# HuUSB_rev_B.net
KiCad netlist of a schematic drawn in EAGLE
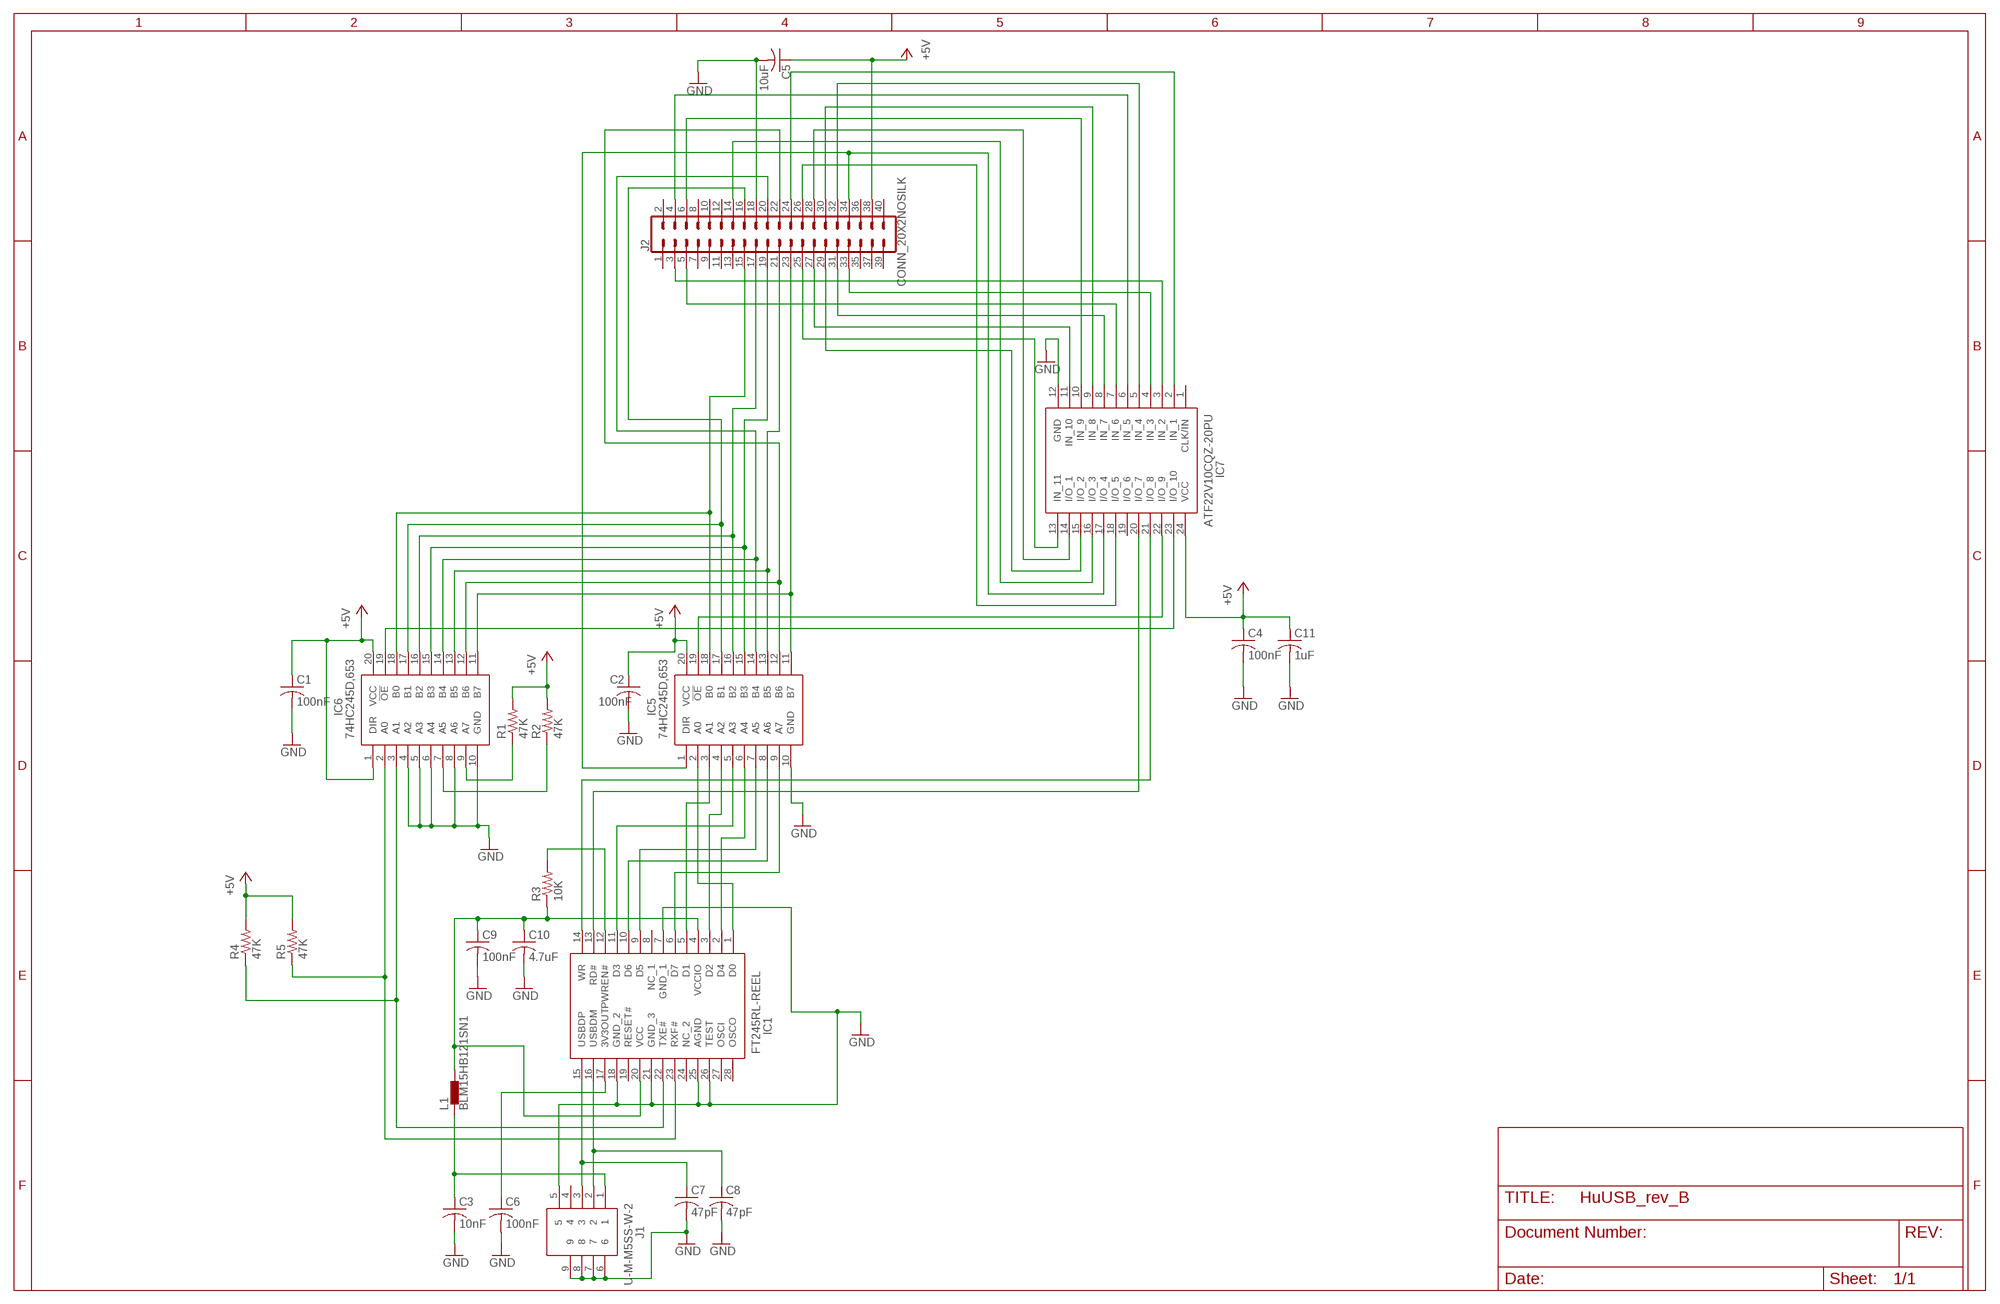
[diagram p0: schematic, sheet 1]

(export (version "E")
  (design (tool "Eeschema 10.0.6"))
  (components
    (comp (ref "C1")
      (value "100nF")
      (footprint "eagle-import:C0603")
      (libsource (lib "eagle-import") (part "C-USC0603"))
    )
    (comp (ref "C2")
      (value "100nF")
      (footprint "eagle-import:C0603")
      (libsource (lib "eagle-import") (part "C-USC0603"))
    )
    (comp (ref "C3")
      (value "10nF")
      (footprint "eagle-import:C0603")
      (libsource (lib "eagle-import") (part "C-USC0603"))
    )
    (comp (ref "C4")
      (value "100nF")
      (footprint "eagle-import:C0603")
      (libsource (lib "eagle-import") (part "C-USC0603"))
    )
    (comp (ref "C5")
      (value "10uF")
      (footprint "eagle-import:C0805")
      (libsource (lib "eagle-import") (part "C-USC0805"))
    )
    (comp (ref "C6")
      (value "100nF")
      (footprint "eagle-import:C0603")
      (libsource (lib "eagle-import") (part "C-USC0603"))
    )
    (comp (ref "C7")
      (value "47pF")
      (footprint "eagle-import:C0603")
      (libsource (lib "eagle-import") (part "C-USC0603"))
    )
    (comp (ref "C8")
      (value "47pF")
      (footprint "eagle-import:C0603")
      (libsource (lib "eagle-import") (part "C-USC0603"))
    )
    (comp (ref "C9")
      (value "100nF")
      (footprint "eagle-import:C0603")
      (libsource (lib "eagle-import") (part "C-USC0603"))
    )
    (comp (ref "C10")
      (value "4.7uF")
      (footprint "eagle-import:C0603")
      (libsource (lib "eagle-import") (part "C-USC0603"))
    )
    (comp (ref "C11")
      (value "1uF")
      (footprint "eagle-import:C0603")
      (libsource (lib "eagle-import") (part "C-USC0603"))
    )
    (comp (ref "IC1")
      (value "FT245RL-REEL")
      (footprint "eagle-import:SOP65P778X200-28N")
      (fields (field (name "MOUSER_PART_NUMBER") "895-FT245RL"))
      (libsource (lib "eagle-import") (part "FT245RL-REEL"))
    )
    (comp (ref "IC5")
      (value "74HC245D,653")
      (footprint "eagle-import:SOIC127P1032X265-20N")
      (fields (field (name "MOUSER_PART_NUMBER") "771-74HC245D-T"))
      (libsource (lib "eagle-import") (part "74HC245D,653"))
    )
    (comp (ref "IC6")
      (value "74HC245D,653")
      (footprint "eagle-import:SOIC127P1032X265-20N")
      (fields (field (name "MOUSER_PART_NUMBER") "771-74HC245D-T"))
      (libsource (lib "eagle-import") (part "74HC245D,653"))
    )
    (comp (ref "IC7")
      (value "ATF22V10CQZ-20PU")
      (footprint "eagle-import:DIP794W56P254L3188H533Q24N")
      (fields (field (name "MOUSER_PART_NUMBER") "556-AF22V10CQZ-20PU"))
      (libsource (lib "eagle-import") (part "ATF22V10CQZ-20PU"))
    )
    (comp (ref "J1")
      (value "U-M-M5SS-W-2")
      (footprint "eagle-import:U-M-M5SS-W-2")
      (libsource (lib "eagle-import") (part "U-M-M5SS-W-2"))
    )
    (comp (ref "J2")
      (value "CONN_20X2NOSILK")
      (footprint "eagle-import:2X20_NOSILK")
      (libsource (lib "eagle-import") (part "CONN_20X2NOSILK"))
    )
    (comp (ref "L1")
      (value "BLM15HB121SN1")
      (footprint "eagle-import:0402")
      (libsource (lib "eagle-import") (part "BLM15HB121SN1"))
    )
    (comp (ref "R1")
      (value "47K")
      (footprint "eagle-import:R0603")
      (libsource (lib "eagle-import") (part "R-US_R0603"))
    )
    (comp (ref "R2")
      (value "47K")
      (footprint "eagle-import:R0603")
      (libsource (lib "eagle-import") (part "R-US_R0603"))
    )
    (comp (ref "R3")
      (value "10K")
      (footprint "eagle-import:R0603")
      (libsource (lib "eagle-import") (part "R-US_R0603"))
    )
    (comp (ref "R4")
      (value "47K")
      (footprint "eagle-import:R0603")
      (libsource (lib "eagle-import") (part "R-US_R0603"))
    )
    (comp (ref "R5")
      (value "47K")
      (footprint "eagle-import:R0603")
      (libsource (lib "eagle-import") (part "R-US_R0603"))
    )
  )
  (nets
    (net (code "1") (name "+5V") (class "Default")
      (node (ref "C1") (pin "1") (pinfunction "1_1") (pintype "passive"))
      (node (ref "C11") (pin "1") (pinfunction "1_1") (pintype "passive"))
      (node (ref "C2") (pin "1") (pinfunction "1_1") (pintype "passive"))
      (node (ref "C4") (pin "1") (pinfunction "1_1") (pintype "passive"))
      (node (ref "C5") (pin "1") (pinfunction "1_1") (pintype "passive"))
      (node (ref "IC5") (pin "20") (pinfunction "VCC_20") (pintype "bidirectional"))
      (node (ref "IC6") (pin "1") (pinfunction "DIR_1") (pintype "bidirectional"))
      (node (ref "IC6") (pin "20") (pinfunction "VCC_20") (pintype "bidirectional"))
      (node (ref "IC7") (pin "24") (pinfunction "VCC_24") (pintype "bidirectional"))
      (node (ref "J2") (pin "38") (pinfunction "38_38") (pintype "passive"))
      (node (ref "R1") (pin "2") (pinfunction "2_2") (pintype "passive"))
      (node (ref "R2") (pin "2") (pinfunction "2_2") (pintype "passive"))
      (node (ref "R4") (pin "2") (pinfunction "2_2") (pintype "passive"))
      (node (ref "R5") (pin "2") (pinfunction "2_2") (pintype "passive"))
    )
    (net (code "2") (name "GND") (class "Default")
      (node (ref "C1") (pin "2") (pinfunction "2_2") (pintype "passive"))
      (node (ref "C10") (pin "2") (pinfunction "2_2") (pintype "passive"))
      (node (ref "C11") (pin "2") (pinfunction "2_2") (pintype "passive"))
      (node (ref "C2") (pin "2") (pinfunction "2_2") (pintype "passive"))
      (node (ref "C3") (pin "2") (pinfunction "2_2") (pintype "passive"))
      (node (ref "C4") (pin "2") (pinfunction "2_2") (pintype "passive"))
      (node (ref "C5") (pin "2") (pinfunction "2_2") (pintype "passive"))
      (node (ref "C6") (pin "2") (pinfunction "2_2") (pintype "passive"))
      (node (ref "C7") (pin "2") (pinfunction "2_2") (pintype "passive"))
      (node (ref "C8") (pin "2") (pinfunction "2_2") (pintype "passive"))
      (node (ref "C9") (pin "2") (pinfunction "2_2") (pintype "passive"))
      (node (ref "IC1") (pin "18") (pinfunction "GND_2_18") (pintype "bidirectional"))
      (node (ref "IC1") (pin "21") (pinfunction "GND_3_21") (pintype "bidirectional"))
      (node (ref "IC1") (pin "25") (pinfunction "AGND_25") (pintype "bidirectional"))
      (node (ref "IC1") (pin "26") (pinfunction "TEST_26") (pintype "bidirectional"))
      (node (ref "IC1") (pin "7") (pinfunction "GND_1_7") (pintype "bidirectional"))
      (node (ref "IC5") (pin "10") (pinfunction "GND_10") (pintype "bidirectional"))
      (node (ref "IC6") (pin "10") (pinfunction "GND_10") (pintype "bidirectional"))
      (node (ref "IC6") (pin "4") (pinfunction "A2_4") (pintype "bidirectional"))
      (node (ref "IC6") (pin "5") (pinfunction "A3_5") (pintype "bidirectional"))
      (node (ref "IC6") (pin "6") (pinfunction "A4_6") (pintype "bidirectional"))
      (node (ref "IC6") (pin "8") (pinfunction "A6_8") (pintype "bidirectional"))
      (node (ref "IC7") (pin "12") (pinfunction "GND_12") (pintype "bidirectional"))
      (node (ref "J1") (pin "5") (pinfunction "5_5") (pintype "bidirectional"))
      (node (ref "J1") (pin "6") (pinfunction "6_6") (pintype "bidirectional"))
      (node (ref "J1") (pin "7") (pinfunction "7_7") (pintype "bidirectional"))
      (node (ref "J1") (pin "8") (pinfunction "8_8") (pintype "bidirectional"))
      (node (ref "J1") (pin "9") (pinfunction "9_9") (pintype "bidirectional"))
      (node (ref "J2") (pin "18") (pinfunction "18_18") (pintype "passive"))
    )
    (net (code "3") (name "Net-(C3-Pad1)") (class "Default")
      (node (ref "C3") (pin "1") (pinfunction "1_1") (pintype "passive"))
      (node (ref "J1") (pin "1") (pinfunction "1_1") (pintype "bidirectional"))
      (node (ref "L1") (pin "1") (pinfunction "1_1") (pintype "passive"))
    )
    (net (code "4") (name "Net-(IC1-3V3OUT)") (class "Default")
      (node (ref "C6") (pin "1") (pinfunction "1_1") (pintype "passive"))
      (node (ref "IC1") (pin "17") (pinfunction "3V3OUT_17") (pintype "bidirectional"))
    )
    (net (code "5") (name "Net-(IC1-D0)") (class "Default")
      (node (ref "IC1") (pin "1") (pinfunction "D0_1") (pintype "bidirectional"))
      (node (ref "IC5") (pin "2") (pinfunction "A0_2") (pintype "bidirectional"))
    )
    (net (code "6") (name "Net-(IC1-D1)") (class "Default")
      (node (ref "IC1") (pin "5") (pinfunction "D1_5") (pintype "bidirectional"))
      (node (ref "IC5") (pin "3") (pinfunction "A1_3") (pintype "bidirectional"))
    )
    (net (code "7") (name "Net-(IC1-D2)") (class "Default")
      (node (ref "IC1") (pin "3") (pinfunction "D2_3") (pintype "bidirectional"))
      (node (ref "IC5") (pin "4") (pinfunction "A2_4") (pintype "bidirectional"))
    )
    (net (code "8") (name "Net-(IC1-D3)") (class "Default")
      (node (ref "IC1") (pin "11") (pinfunction "D3_11") (pintype "bidirectional"))
      (node (ref "IC5") (pin "5") (pinfunction "A3_5") (pintype "bidirectional"))
    )
    (net (code "9") (name "Net-(IC1-D4)") (class "Default")
      (node (ref "IC1") (pin "2") (pinfunction "D4_2") (pintype "bidirectional"))
      (node (ref "IC5") (pin "6") (pinfunction "A4_6") (pintype "bidirectional"))
    )
    (net (code "10") (name "Net-(IC1-D5)") (class "Default")
      (node (ref "IC1") (pin "9") (pinfunction "D5_9") (pintype "bidirectional"))
      (node (ref "IC5") (pin "7") (pinfunction "A5_7") (pintype "bidirectional"))
    )
    (net (code "11") (name "Net-(IC1-D6)") (class "Default")
      (node (ref "IC1") (pin "10") (pinfunction "D6_10") (pintype "bidirectional"))
      (node (ref "IC5") (pin "8") (pinfunction "A6_8") (pintype "bidirectional"))
    )
    (net (code "12") (name "Net-(IC1-D7)") (class "Default")
      (node (ref "IC1") (pin "6") (pinfunction "D7_6") (pintype "bidirectional"))
      (node (ref "IC5") (pin "9") (pinfunction "A7_9") (pintype "bidirectional"))
    )
    (net (code "13") (name "Net-(IC1-PWREN#)") (class "Default")
      (node (ref "IC1") (pin "12") (pinfunction "PWREN#_12") (pintype "bidirectional"))
      (node (ref "R3") (pin "2") (pinfunction "2_2") (pintype "passive"))
    )
    (net (code "14") (name "Net-(IC1-RD#)") (class "Default")
      (node (ref "IC1") (pin "13") (pinfunction "RD#_13") (pintype "bidirectional"))
      (node (ref "IC7") (pin "20") (pinfunction "I/O_7_20") (pintype "bidirectional"))
    )
    (net (code "15") (name "Net-(IC1-RXF#)") (class "Default")
      (node (ref "IC1") (pin "23") (pinfunction "RXF#_23") (pintype "bidirectional"))
      (node (ref "IC6") (pin "2") (pinfunction "A0_2") (pintype "bidirectional"))
      (node (ref "R5") (pin "1") (pinfunction "1_1") (pintype "passive"))
    )
    (net (code "16") (name "Net-(IC1-TXE#)") (class "Default")
      (node (ref "IC1") (pin "22") (pinfunction "TXE#_22") (pintype "bidirectional"))
      (node (ref "IC6") (pin "3") (pinfunction "A1_3") (pintype "bidirectional"))
      (node (ref "R4") (pin "1") (pinfunction "1_1") (pintype "passive"))
    )
    (net (code "17") (name "Net-(IC1-USBDM)") (class "Default")
      (node (ref "C8") (pin "1") (pinfunction "1_1") (pintype "passive"))
      (node (ref "IC1") (pin "16") (pinfunction "USBDM_16") (pintype "bidirectional"))
      (node (ref "J1") (pin "2") (pinfunction "2_2") (pintype "bidirectional"))
    )
    (net (code "18") (name "Net-(IC1-USBDP)") (class "Default")
      (node (ref "C7") (pin "1") (pinfunction "1_1") (pintype "passive"))
      (node (ref "IC1") (pin "15") (pinfunction "USBDP_15") (pintype "bidirectional"))
      (node (ref "J1") (pin "3") (pinfunction "3_3") (pintype "bidirectional"))
    )
    (net (code "19") (name "Net-(IC1-VCC)") (class "Default")
      (node (ref "C10") (pin "1") (pinfunction "1_1") (pintype "passive"))
      (node (ref "C9") (pin "1") (pinfunction "1_1") (pintype "passive"))
      (node (ref "IC1") (pin "20") (pinfunction "VCC_20") (pintype "bidirectional"))
      (node (ref "IC1") (pin "4") (pinfunction "VCCIO_4") (pintype "bidirectional"))
      (node (ref "L1") (pin "2") (pinfunction "2_2") (pintype "passive"))
      (node (ref "R3") (pin "1") (pinfunction "1_1") (pintype "passive"))
    )
    (net (code "20") (name "Net-(IC1-WR)") (class "Default")
      (node (ref "IC1") (pin "14") (pinfunction "WR_14") (pintype "bidirectional"))
      (node (ref "IC7") (pin "21") (pinfunction "I/O_8_21") (pintype "bidirectional"))
    )
    (net (code "21") (name "Net-(IC5-B0)") (class "Default")
      (node (ref "IC5") (pin "18") (pinfunction "B0_18") (pintype "bidirectional"))
      (node (ref "IC6") (pin "18") (pinfunction "B0_18") (pintype "bidirectional"))
      (node (ref "J2") (pin "15") (pinfunction "15_15") (pintype "passive"))
    )
    (net (code "22") (name "Net-(IC5-B1)") (class "Default")
      (node (ref "IC5") (pin "17") (pinfunction "B1_17") (pintype "bidirectional"))
      (node (ref "IC6") (pin "17") (pinfunction "B1_17") (pintype "bidirectional"))
      (node (ref "J2") (pin "16") (pinfunction "16_16") (pintype "passive"))
    )
    (net (code "23") (name "Net-(IC5-B2)") (class "Default")
      (node (ref "IC5") (pin "16") (pinfunction "B2_16") (pintype "bidirectional"))
      (node (ref "IC6") (pin "16") (pinfunction "B2_16") (pintype "bidirectional"))
      (node (ref "J2") (pin "17") (pinfunction "17_17") (pintype "passive"))
    )
    (net (code "24") (name "Net-(IC5-B3)") (class "Default")
      (node (ref "IC5") (pin "15") (pinfunction "B3_15") (pintype "bidirectional"))
      (node (ref "IC6") (pin "15") (pinfunction "B3_15") (pintype "bidirectional"))
      (node (ref "J2") (pin "19") (pinfunction "19_19") (pintype "passive"))
    )
    (net (code "25") (name "Net-(IC5-B4)") (class "Default")
      (node (ref "IC5") (pin "14") (pinfunction "B4_14") (pintype "bidirectional"))
      (node (ref "IC6") (pin "14") (pinfunction "B4_14") (pintype "bidirectional"))
      (node (ref "J2") (pin "20") (pinfunction "20_20") (pintype "passive"))
    )
    (net (code "26") (name "Net-(IC5-B5)") (class "Default")
      (node (ref "IC5") (pin "13") (pinfunction "B5_13") (pintype "bidirectional"))
      (node (ref "IC6") (pin "13") (pinfunction "B5_13") (pintype "bidirectional"))
      (node (ref "J2") (pin "21") (pinfunction "21_21") (pintype "passive"))
    )
    (net (code "27") (name "Net-(IC5-B6)") (class "Default")
      (node (ref "IC5") (pin "12") (pinfunction "B6_12") (pintype "bidirectional"))
      (node (ref "IC6") (pin "12") (pinfunction "B6_12") (pintype "bidirectional"))
      (node (ref "J2") (pin "22") (pinfunction "22_22") (pintype "passive"))
    )
    (net (code "28") (name "Net-(IC5-B7)") (class "Default")
      (node (ref "IC5") (pin "11") (pinfunction "B7_11") (pintype "bidirectional"))
      (node (ref "IC6") (pin "11") (pinfunction "B7_11") (pintype "bidirectional"))
      (node (ref "J2") (pin "23") (pinfunction "23_23") (pintype "passive"))
    )
    (net (code "29") (name "Net-(IC5-DIR)") (class "Default")
      (node (ref "IC5") (pin "1") (pinfunction "DIR_1") (pintype "bidirectional"))
      (node (ref "IC7") (pin "17") (pinfunction "I/O_4_17") (pintype "bidirectional"))
      (node (ref "J2") (pin "34") (pinfunction "34_34") (pintype "passive"))
    )
    (net (code "30") (name "Net-(IC5-~{OE})") (class "Default")
      (node (ref "IC5") (pin "19") (pinfunction "~{OE}_19") (pintype "bidirectional"))
      (node (ref "IC7") (pin "22") (pinfunction "I/O_9_22") (pintype "bidirectional"))
    )
    (net (code "31") (name "Net-(IC6-A5)") (class "Default")
      (node (ref "IC6") (pin "7") (pinfunction "A5_7") (pintype "bidirectional"))
      (node (ref "R2") (pin "1") (pinfunction "1_1") (pintype "passive"))
    )
    (net (code "32") (name "Net-(IC6-A7)") (class "Default")
      (node (ref "IC6") (pin "9") (pinfunction "A7_9") (pintype "bidirectional"))
      (node (ref "R1") (pin "1") (pinfunction "1_1") (pintype "passive"))
    )
    (net (code "33") (name "Net-(IC6-~{OE})") (class "Default")
      (node (ref "IC6") (pin "19") (pinfunction "~{OE}_19") (pintype "bidirectional"))
      (node (ref "IC7") (pin "23") (pinfunction "I/O_10_23") (pintype "bidirectional"))
    )
    (net (code "34") (name "Net-(IC7-IN_1)") (class "Default")
      (node (ref "IC7") (pin "2") (pinfunction "IN_1_2") (pintype "bidirectional"))
      (node (ref "J2") (pin "24") (pinfunction "24_24") (pintype "passive"))
    )
    (net (code "35") (name "Net-(IC7-IN_2)") (class "Default")
      (node (ref "IC7") (pin "3") (pinfunction "IN_2_3") (pintype "bidirectional"))
      (node (ref "J2") (pin "3") (pinfunction "3_3") (pintype "passive"))
    )
    (net (code "36") (name "Net-(IC7-IN_3)") (class "Default")
      (node (ref "IC7") (pin "4") (pinfunction "IN_3_4") (pintype "bidirectional"))
      (node (ref "J2") (pin "33") (pinfunction "33_33") (pintype "passive"))
    )
    (net (code "37") (name "Net-(IC7-IN_4)") (class "Default")
      (node (ref "IC7") (pin "5") (pinfunction "IN_4_5") (pintype "bidirectional"))
      (node (ref "J2") (pin "32") (pinfunction "32_32") (pintype "passive"))
    )
    (net (code "38") (name "Net-(IC7-IN_5)") (class "Default")
      (node (ref "IC7") (pin "6") (pinfunction "IN_5_6") (pintype "bidirectional"))
      (node (ref "J2") (pin "4") (pinfunction "4_4") (pintype "passive"))
    )
    (net (code "39") (name "Net-(IC7-IN_6)") (class "Default")
      (node (ref "IC7") (pin "7") (pinfunction "IN_6_7") (pintype "bidirectional"))
      (node (ref "J2") (pin "5") (pinfunction "5_5") (pintype "passive"))
    )
    (net (code "40") (name "Net-(IC7-IN_7)") (class "Default")
      (node (ref "IC7") (pin "8") (pinfunction "IN_7_8") (pintype "bidirectional"))
      (node (ref "J2") (pin "31") (pinfunction "31_31") (pintype "passive"))
    )
    (net (code "41") (name "Net-(IC7-IN_8)") (class "Default")
      (node (ref "IC7") (pin "9") (pinfunction "IN_8_9") (pintype "bidirectional"))
      (node (ref "J2") (pin "30") (pinfunction "30_30") (pintype "passive"))
    )
    (net (code "42") (name "Net-(IC7-IN_9)") (class "Default")
      (node (ref "IC7") (pin "10") (pinfunction "IN_9_10") (pintype "bidirectional"))
      (node (ref "J2") (pin "6") (pinfunction "6_6") (pintype "passive"))
    )
    (net (code "43") (name "Net-(IC7-IN_10)") (class "Default")
      (node (ref "IC7") (pin "11") (pinfunction "IN_10_11") (pintype "bidirectional"))
      (node (ref "J2") (pin "27") (pinfunction "27_27") (pintype "passive"))
    )
    (net (code "44") (name "Net-(IC7-IN_11)") (class "Default")
      (node (ref "IC7") (pin "13") (pinfunction "IN_11_13") (pintype "bidirectional"))
      (node (ref "J2") (pin "25") (pinfunction "25_25") (pintype "passive"))
    )
    (net (code "45") (name "Net-(IC7-I{slash}O_1)") (class "Default")
      (node (ref "IC7") (pin "14") (pinfunction "I/O_1_14") (pintype "bidirectional"))
      (node (ref "J2") (pin "28") (pinfunction "28_28") (pintype "passive"))
    )
    (net (code "46") (name "Net-(IC7-I{slash}O_2)") (class "Default")
      (node (ref "IC7") (pin "15") (pinfunction "I/O_2_15") (pintype "bidirectional"))
      (node (ref "J2") (pin "29") (pinfunction "29_29") (pintype "passive"))
    )
    (net (code "47") (name "Net-(IC7-I{slash}O_3)") (class "Default")
      (node (ref "IC7") (pin "16") (pinfunction "I/O_3_16") (pintype "bidirectional"))
      (node (ref "J2") (pin "14") (pinfunction "14_14") (pintype "passive"))
    )
    (net (code "48") (name "Net-(IC7-I{slash}O_5)") (class "Default")
      (node (ref "IC7") (pin "18") (pinfunction "I/O_5_18") (pintype "bidirectional"))
      (node (ref "J2") (pin "26") (pinfunction "26_26") (pintype "passive"))
    )
    (net (code "49") (name "unconnected-(IC1-NC_1-Pad8)") (class "Default")
      (node (ref "IC1") (pin "8") (pinfunction "NC_1_8") (pintype "bidirectional"))
    )
    (net (code "50") (name "unconnected-(IC1-NC_2-Pad24)") (class "Default")
      (node (ref "IC1") (pin "24") (pinfunction "NC_2_24") (pintype "bidirectional"))
    )
    (net (code "51") (name "unconnected-(IC1-OSCI-Pad27)") (class "Default")
      (node (ref "IC1") (pin "27") (pinfunction "OSCI_27") (pintype "bidirectional"))
    )
    (net (code "52") (name "unconnected-(IC1-OSCO-Pad28)") (class "Default")
      (node (ref "IC1") (pin "28") (pinfunction "OSCO_28") (pintype "bidirectional"))
    )
    (net (code "53") (name "unconnected-(IC1-RESET#-Pad19)") (class "Default")
      (node (ref "IC1") (pin "19") (pinfunction "RESET#_19") (pintype "bidirectional"))
    )
    (net (code "54") (name "unconnected-(IC7-CLK{slash}IN-Pad1)") (class "Default")
      (node (ref "IC7") (pin "1") (pinfunction "CLK/IN_1") (pintype "bidirectional"))
    )
    (net (code "55") (name "unconnected-(IC7-I{slash}O_6-Pad19)") (class "Default")
      (node (ref "IC7") (pin "19") (pinfunction "I/O_6_19") (pintype "bidirectional"))
    )
    (net (code "56") (name "unconnected-(J1-Pad4)") (class "Default")
      (node (ref "J1") (pin "4") (pinfunction "4_4") (pintype "bidirectional"))
    )
    (net (code "57") (name "unconnected-(J2-Pad1)") (class "Default")
      (node (ref "J2") (pin "1") (pinfunction "1_1") (pintype "passive"))
    )
    (net (code "58") (name "unconnected-(J2-Pad2)") (class "Default")
      (node (ref "J2") (pin "2") (pinfunction "2_2") (pintype "passive"))
    )
    (net (code "59") (name "unconnected-(J2-Pad7)") (class "Default")
      (node (ref "J2") (pin "7") (pinfunction "7_7") (pintype "passive"))
    )
    (net (code "60") (name "unconnected-(J2-Pad8)") (class "Default")
      (node (ref "J2") (pin "8") (pinfunction "8_8") (pintype "passive"))
    )
    (net (code "61") (name "unconnected-(J2-Pad9)") (class "Default")
      (node (ref "J2") (pin "9") (pinfunction "9_9") (pintype "passive"))
    )
    (net (code "62") (name "unconnected-(J2-Pad10)") (class "Default")
      (node (ref "J2") (pin "10") (pinfunction "10_10") (pintype "passive"))
    )
    (net (code "63") (name "unconnected-(J2-Pad11)") (class "Default")
      (node (ref "J2") (pin "11") (pinfunction "11_11") (pintype "passive"))
    )
    (net (code "64") (name "unconnected-(J2-Pad12)") (class "Default")
      (node (ref "J2") (pin "12") (pinfunction "12_12") (pintype "passive"))
    )
    (net (code "65") (name "unconnected-(J2-Pad13)") (class "Default")
      (node (ref "J2") (pin "13") (pinfunction "13_13") (pintype "passive"))
    )
    (net (code "66") (name "unconnected-(J2-Pad35)") (class "Default")
      (node (ref "J2") (pin "35") (pinfunction "35_35") (pintype "passive"))
    )
    (net (code "67") (name "unconnected-(J2-Pad36)") (class "Default")
      (node (ref "J2") (pin "36") (pinfunction "36_36") (pintype "passive"))
    )
    (net (code "68") (name "unconnected-(J2-Pad37)") (class "Default")
      (node (ref "J2") (pin "37") (pinfunction "37_37") (pintype "passive"))
    )
    (net (code "69") (name "unconnected-(J2-Pad39)") (class "Default")
      (node (ref "J2") (pin "39") (pinfunction "39_39") (pintype "passive"))
    )
    (net (code "70") (name "unconnected-(J2-Pad40)") (class "Default")
      (node (ref "J2") (pin "40") (pinfunction "40_40") (pintype "passive"))
    )
  )
)
